# PI_Tank_level_controller.net
KiCad netlist of a schematic drawn in EAGLE
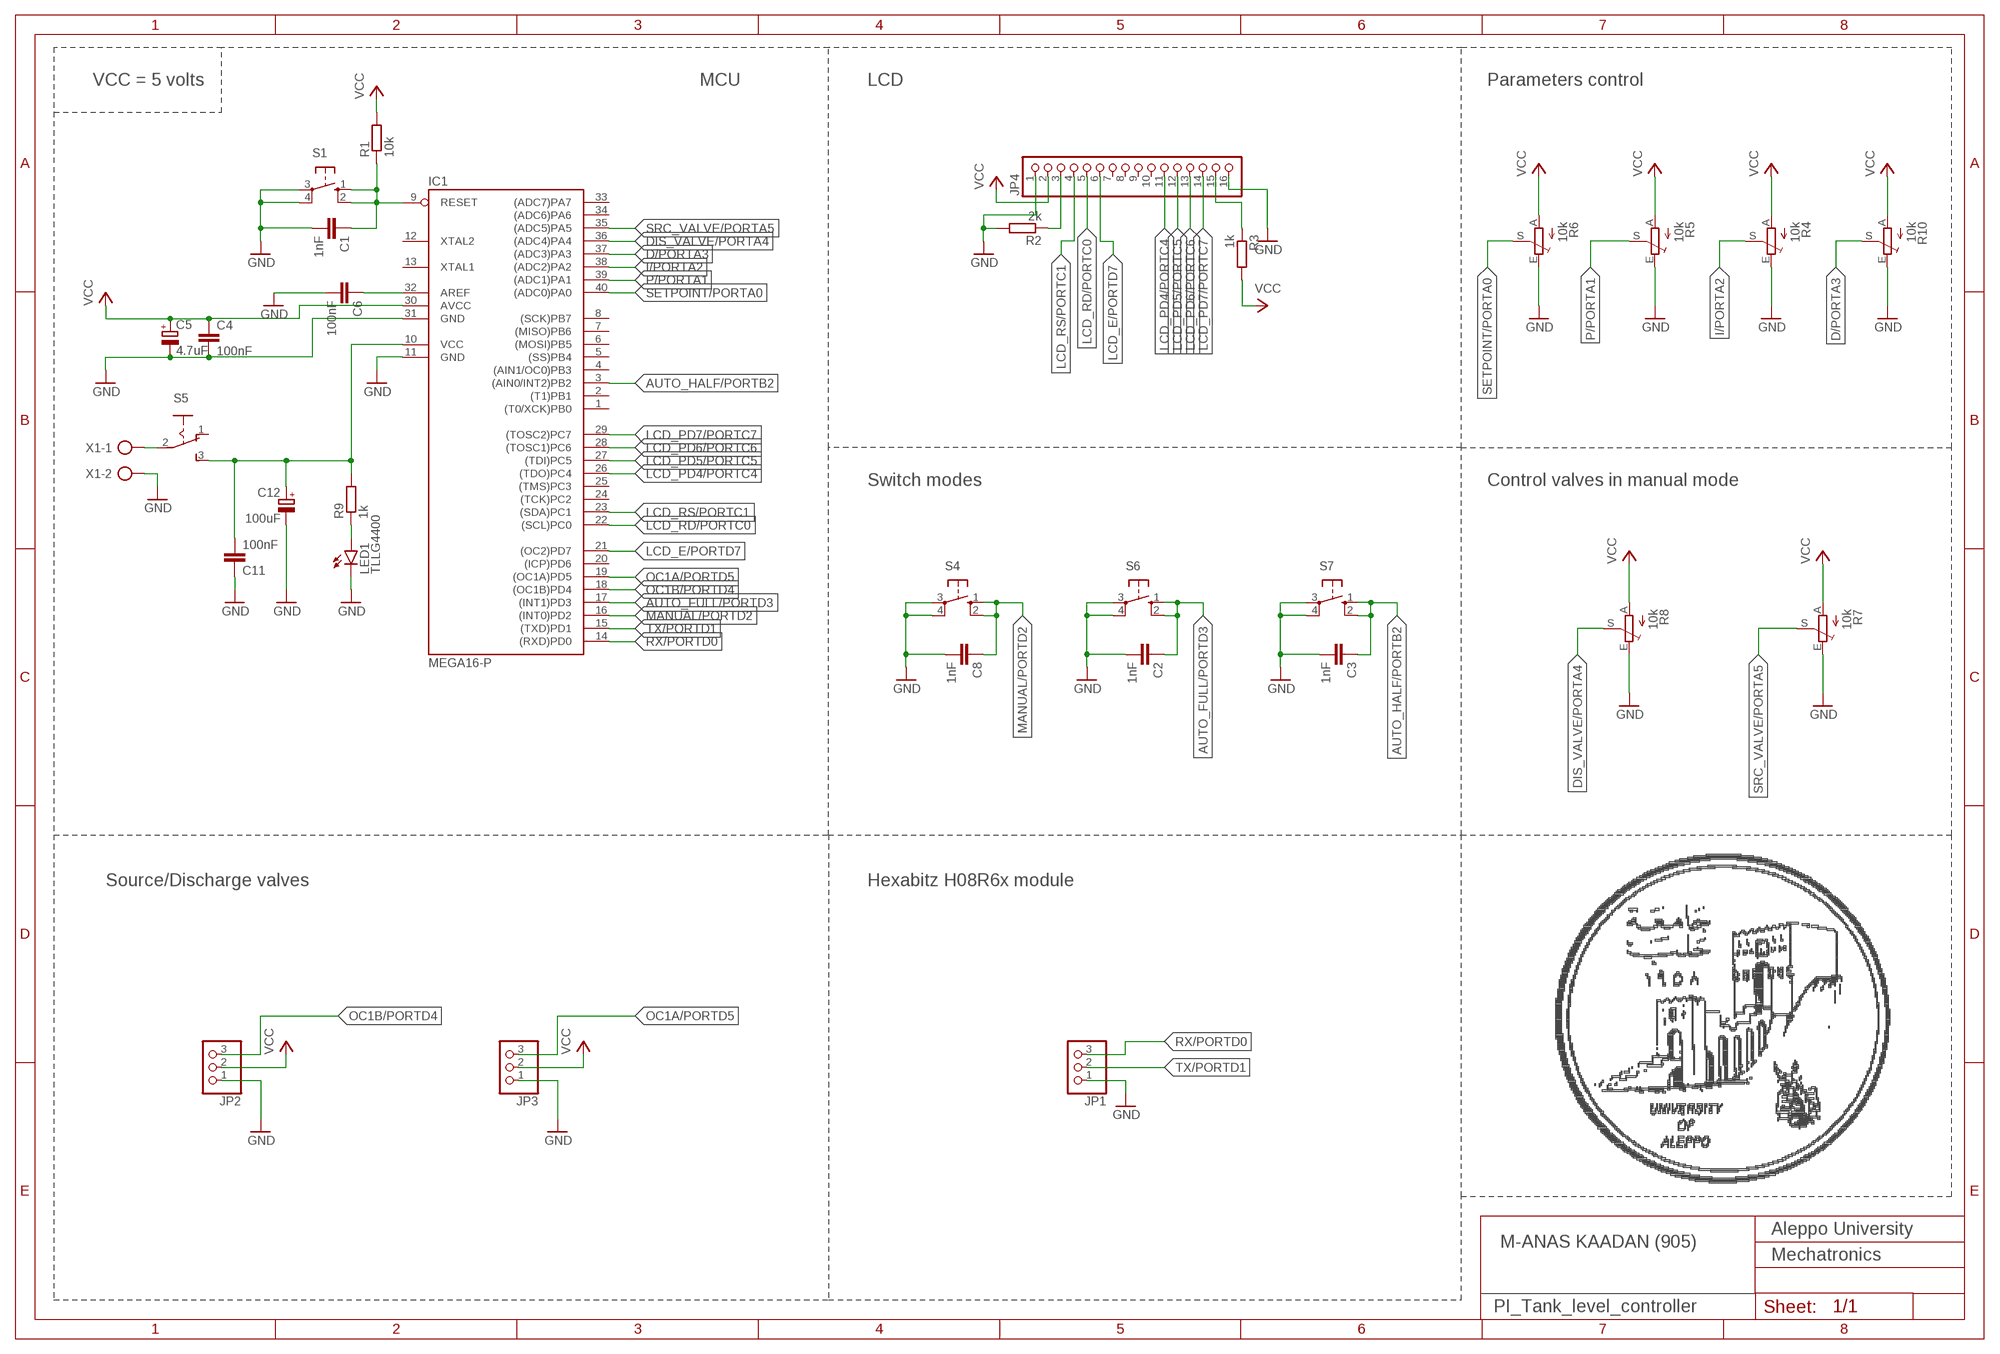
[diagram p0: schematic, sheet 1]

(export (version "E")
  (design (tool "Eeschema 10.0.6"))
  (components
    (comp (ref "C1")
      (value "1nF")
      (footprint "eagle-import:C025-024X044")
      (libsource (lib "eagle-import") (part "rcl_334_C-EU025-024X044"))
    )
    (comp (ref "C2")
      (value "1nF")
      (footprint "eagle-import:C025-024X044")
      (libsource (lib "eagle-import") (part "rcl_334_C-EU025-024X044"))
    )
    (comp (ref "C3")
      (value "1nF")
      (footprint "eagle-import:C025-024X044")
      (libsource (lib "eagle-import") (part "rcl_334_C-EU025-024X044"))
    )
    (comp (ref "C4")
      (value "100nF")
      (footprint "eagle-import:C025-024X044")
      (libsource (lib "eagle-import") (part "rcl_334_C-EU025-024X044"))
    )
    (comp (ref "C5")
      (value "4.7uF")
      (footprint "eagle-import:E2,5-6E")
      (libsource (lib "eagle-import") (part "rcl_334_CPOL-EUE2,5-6E"))
    )
    (comp (ref "C6")
      (value "100nF")
      (footprint "eagle-import:C025-024X044")
      (libsource (lib "eagle-import") (part "rcl_334_C-EU025-024X044"))
    )
    (comp (ref "C8")
      (value "1nF")
      (footprint "eagle-import:C025-024X044")
      (libsource (lib "eagle-import") (part "rcl_334_C-EU025-024X044"))
    )
    (comp (ref "C11")
      (value "100nF")
      (footprint "eagle-import:C025-024X044")
      (libsource (lib "eagle-import") (part "C-EU025-024X044"))
    )
    (comp (ref "C12")
      (value "100uF")
      (footprint "eagle-import:B45181A")
      (libsource (lib "eagle-import") (part "CPOL-EUB45181A"))
    )
    (comp (ref "IC1")
      (value "MEGA16-P")
      (footprint "eagle-import:DIL40")
      (fields (field (name "MPN") "ATMEGA16-16PU"))
      (libsource (lib "eagle-import") (part "MEGA16-P"))
    )
    (comp (ref "JP1")
      (value "PINHD-1X3")
      (footprint "eagle-import:1X03")
      (libsource (lib "eagle-import") (part "PINHD-1X3"))
    )
    (comp (ref "JP2")
      (value "PINHD-1X3")
      (footprint "eagle-import:1X03")
      (libsource (lib "eagle-import") (part "PINHD-1X3"))
    )
    (comp (ref "JP3")
      (value "PINHD-1X3")
      (footprint "eagle-import:1X03")
      (libsource (lib "eagle-import") (part "PINHD-1X3"))
    )
    (comp (ref "JP4")
      (value "PINHD-1X16")
      (footprint "eagle-import:1X16")
      (libsource (lib "eagle-import") (part "PINHD-1X16"))
    )
    (comp (ref "LED1")
      (value "TLLG4400")
      (footprint "eagle-import:LED3MM")
      (fields (field (name "MF") "VISHAY SEMICONDUCTOR"))
      (libsource (lib "eagle-import") (part "TLLG4400"))
    )
    (comp (ref "R1")
      (value "10k")
      (footprint "eagle-import:0204_7")
      (libsource (lib "eagle-import") (part "rcl_334_R-EU_0204/7"))
    )
    (comp (ref "R2")
      (value "2k")
      (footprint "eagle-import:0204_7")
      (libsource (lib "eagle-import") (part "rcl_334_R-EU_0204/7"))
    )
    (comp (ref "R3")
      (value "1k")
      (footprint "eagle-import:0204_7")
      (libsource (lib "eagle-import") (part "rcl_334_R-EU_0204/7"))
    )
    (comp (ref "R4")
      (value "10k")
      (footprint "eagle-import:RJ9W")
      (libsource (lib "eagle-import") (part "TRIM_EU-RJ9W"))
    )
    (comp (ref "R5")
      (value "10k")
      (footprint "eagle-import:RJ9W")
      (libsource (lib "eagle-import") (part "TRIM_EU-RJ9W"))
    )
    (comp (ref "R6")
      (value "10k")
      (footprint "eagle-import:RJ9W")
      (libsource (lib "eagle-import") (part "TRIM_EU-RJ9W"))
    )
    (comp (ref "R7")
      (value "10k")
      (footprint "eagle-import:RJ9W")
      (libsource (lib "eagle-import") (part "TRIM_EU-RJ9W"))
    )
    (comp (ref "R8")
      (value "10k")
      (footprint "eagle-import:RJ9W")
      (libsource (lib "eagle-import") (part "TRIM_EU-RJ9W"))
    )
    (comp (ref "R9")
      (value "1k")
      (footprint "eagle-import:0204_7")
      (libsource (lib "eagle-import") (part "R-EU_0204/7"))
    )
    (comp (ref "R10")
      (value "10k")
      (footprint "eagle-import:RJ9W")
      (libsource (lib "eagle-import") (part "TRIM_EU-RJ9W"))
    )
    (comp (ref "S1")
      (value "10-XX")
      (footprint "eagle-import:B3F-10XX")
      (fields (field (name "MPN") "B3F-1000"))
      (libsource (lib "eagle-import") (part "10-XX"))
    )
    (comp (ref "S4")
      (value "10-XX")
      (footprint "eagle-import:B3F-10XX")
      (fields (field (name "MPN") "B3F-1000"))
      (libsource (lib "eagle-import") (part "10-XX"))
    )
    (comp (ref "S5")
      (value "255SB")
      (footprint "eagle-import:255SB")
      (libsource (lib "eagle-import") (part "255SB"))
    )
    (comp (ref "S6")
      (value "10-XX")
      (footprint "eagle-import:B3F-10XX")
      (fields (field (name "MPN") "B3F-1000"))
      (libsource (lib "eagle-import") (part "10-XX"))
    )
    (comp (ref "S7")
      (value "10-XX")
      (footprint "eagle-import:B3F-10XX")
      (fields (field (name "MPN") "B3F-1000"))
      (libsource (lib "eagle-import") (part "10-XX"))
    )
    (comp (ref "X1")
      (value "AK300/2")
      (footprint "eagle-import:AK300_2")
      (libsource (lib "eagle-import") (part "AK300/2"))
    )
  )
  (nets
    (net (code "1") (name "AUTO_FULL{slash}PORTD3") (class "Default")
      (node (ref "C2") (pin "1") (pinfunction "1_1") (pintype "passive"))
      (node (ref "IC1") (pin "17") (pinfunction "(INT1)PD3_17") (pintype "bidirectional"))
      (node (ref "S6") (pin "1") (pinfunction "S_1") (pintype "passive"))
      (node (ref "S6") (pin "2") (pinfunction "S1_2") (pintype "passive"))
    )
    (net (code "2") (name "AUTO_HALF{slash}PORTB2") (class "Default")
      (node (ref "C3") (pin "1") (pinfunction "1_1") (pintype "passive"))
      (node (ref "IC1") (pin "3") (pinfunction "(AIN0/INT2)PB2_3") (pintype "bidirectional"))
      (node (ref "S7") (pin "1") (pinfunction "S_1") (pintype "passive"))
      (node (ref "S7") (pin "2") (pinfunction "S1_2") (pintype "passive"))
    )
    (net (code "3") (name "DIS_VALVE{slash}PORTA4") (class "Default")
      (node (ref "IC1") (pin "36") (pinfunction "(ADC4)PA4_36") (pintype "bidirectional"))
      (node (ref "R8") (pin "S") (pinfunction "S_S") (pintype "passive"))
    )
    (net (code "4") (name "D{slash}PORTA3") (class "Default")
      (node (ref "IC1") (pin "37") (pinfunction "(ADC3)PA3_37") (pintype "bidirectional"))
      (node (ref "R10") (pin "S") (pinfunction "S_S") (pintype "passive"))
    )
    (net (code "5") (name "GND") (class "Default")
      (node (ref "C1") (pin "2") (pinfunction "2_2") (pintype "passive"))
      (node (ref "C11") (pin "1") (pinfunction "1_1") (pintype "passive"))
      (node (ref "C12") (pin "-") (pinfunction "-_-") (pintype "passive"))
      (node (ref "C2") (pin "2") (pinfunction "2_2") (pintype "passive"))
      (node (ref "C3") (pin "2") (pinfunction "2_2") (pintype "passive"))
      (node (ref "C4") (pin "2") (pinfunction "2_2") (pintype "passive"))
      (node (ref "C5") (pin "-") (pinfunction "-_-") (pintype "passive"))
      (node (ref "C6") (pin "2") (pinfunction "2_2") (pintype "passive"))
      (node (ref "C8") (pin "2") (pinfunction "2_2") (pintype "passive"))
      (node (ref "IC1") (pin "11") (pinfunction "GND_11") (pintype "power_in"))
      (node (ref "IC1") (pin "31") (pinfunction "GND_31") (pintype "power_in"))
      (node (ref "JP1") (pin "1") (pinfunction "1_1") (pintype "passive"))
      (node (ref "JP2") (pin "1") (pinfunction "1_1") (pintype "passive"))
      (node (ref "JP3") (pin "1") (pinfunction "1_1") (pintype "passive"))
      (node (ref "JP4") (pin "1") (pinfunction "1_1") (pintype "passive"))
      (node (ref "JP4") (pin "16") (pinfunction "16_16") (pintype "passive"))
      (node (ref "LED1") (pin "K") (pinfunction "C_K") (pintype "passive"))
      (node (ref "R10") (pin "E") (pinfunction "E_E") (pintype "passive"))
      (node (ref "R2") (pin "2") (pinfunction "2_2") (pintype "passive"))
      (node (ref "R4") (pin "E") (pinfunction "E_E") (pintype "passive"))
      (node (ref "R5") (pin "E") (pinfunction "E_E") (pintype "passive"))
      (node (ref "R6") (pin "E") (pinfunction "E_E") (pintype "passive"))
      (node (ref "R7") (pin "E") (pinfunction "E_E") (pintype "passive"))
      (node (ref "R8") (pin "E") (pinfunction "E_E") (pintype "passive"))
      (node (ref "S1") (pin "3") (pinfunction "P_3") (pintype "passive"))
      (node (ref "S1") (pin "4") (pinfunction "P1_4") (pintype "passive"))
      (node (ref "S4") (pin "3") (pinfunction "P_3") (pintype "passive"))
      (node (ref "S4") (pin "4") (pinfunction "P1_4") (pintype "passive"))
      (node (ref "S6") (pin "3") (pinfunction "P_3") (pintype "passive"))
      (node (ref "S6") (pin "4") (pinfunction "P1_4") (pintype "passive"))
      (node (ref "S7") (pin "3") (pinfunction "P_3") (pintype "passive"))
      (node (ref "S7") (pin "4") (pinfunction "P1_4") (pintype "passive"))
      (node (ref "X1") (pin "2") (pinfunction "KL_2") (pintype "passive"))
    )
    (net (code "6") (name "I{slash}PORTA2") (class "Default")
      (node (ref "IC1") (pin "38") (pinfunction "(ADC2)PA2_38") (pintype "bidirectional"))
      (node (ref "R4") (pin "S") (pinfunction "S_S") (pintype "passive"))
    )
    (net (code "7") (name "LCD_E{slash}PORTD7") (class "Default")
      (node (ref "IC1") (pin "21") (pinfunction "(OC2)PD7_21") (pintype "bidirectional"))
      (node (ref "JP4") (pin "6") (pinfunction "6_6") (pintype "passive"))
    )
    (net (code "8") (name "LCD_PD4{slash}PORTC4") (class "Default")
      (node (ref "IC1") (pin "26") (pinfunction "(TDO)PC4_26") (pintype "bidirectional"))
      (node (ref "JP4") (pin "11") (pinfunction "11_11") (pintype "passive"))
    )
    (net (code "9") (name "LCD_PD5{slash}PORTC5") (class "Default")
      (node (ref "IC1") (pin "27") (pinfunction "(TDI)PC5_27") (pintype "bidirectional"))
      (node (ref "JP4") (pin "12") (pinfunction "12_12") (pintype "passive"))
    )
    (net (code "10") (name "LCD_PD6{slash}PORTC6") (class "Default")
      (node (ref "IC1") (pin "28") (pinfunction "(TOSC1)PC6_28") (pintype "bidirectional"))
      (node (ref "JP4") (pin "13") (pinfunction "13_13") (pintype "passive"))
    )
    (net (code "11") (name "LCD_PD7{slash}PORTC7") (class "Default")
      (node (ref "IC1") (pin "29") (pinfunction "(TOSC2)PC7_29") (pintype "bidirectional"))
      (node (ref "JP4") (pin "14") (pinfunction "14_14") (pintype "passive"))
    )
    (net (code "12") (name "LCD_RD{slash}PORTC0") (class "Default")
      (node (ref "IC1") (pin "22") (pinfunction "(SCL)PC0_22") (pintype "bidirectional"))
      (node (ref "JP4") (pin "5") (pinfunction "5_5") (pintype "passive"))
    )
    (net (code "13") (name "LCD_RS{slash}PORTC1") (class "Default")
      (node (ref "IC1") (pin "23") (pinfunction "(SDA)PC1_23") (pintype "bidirectional"))
      (node (ref "JP4") (pin "4") (pinfunction "4_4") (pintype "passive"))
    )
    (net (code "14") (name "MANUAL{slash}PORTD2") (class "Default")
      (node (ref "C8") (pin "1") (pinfunction "1_1") (pintype "passive"))
      (node (ref "IC1") (pin "16") (pinfunction "(INT0)PD2_16") (pintype "bidirectional"))
      (node (ref "S4") (pin "1") (pinfunction "S_1") (pintype "passive"))
      (node (ref "S4") (pin "2") (pinfunction "S1_2") (pintype "passive"))
    )
    (net (code "15") (name "Net-(IC1-AREF)") (class "Default")
      (node (ref "C6") (pin "1") (pinfunction "1_1") (pintype "passive"))
      (node (ref "IC1") (pin "32") (pinfunction "AREF_32") (pintype "passive"))
    )
    (net (code "16") (name "Net-(IC1-RESET)") (class "Default")
      (node (ref "C1") (pin "1") (pinfunction "1_1") (pintype "passive"))
      (node (ref "IC1") (pin "9") (pinfunction "RESET_9") (pintype "input"))
      (node (ref "R1") (pin "1") (pinfunction "1_1") (pintype "passive"))
      (node (ref "S1") (pin "1") (pinfunction "S_1") (pintype "passive"))
      (node (ref "S1") (pin "2") (pinfunction "S1_2") (pintype "passive"))
    )
    (net (code "17") (name "Net-(JP4-Pad3)") (class "Default")
      (node (ref "JP4") (pin "3") (pinfunction "3_3") (pintype "passive"))
      (node (ref "R2") (pin "1") (pinfunction "1_1") (pintype "passive"))
    )
    (net (code "18") (name "Net-(JP4-Pad15)") (class "Default")
      (node (ref "JP4") (pin "15") (pinfunction "15_15") (pintype "passive"))
      (node (ref "R3") (pin "1") (pinfunction "1_1") (pintype "passive"))
    )
    (net (code "19") (name "Net-(LED1-PadA)") (class "Default")
      (node (ref "LED1") (pin "A") (pinfunction "A_A") (pintype "passive"))
      (node (ref "R9") (pin "1") (pinfunction "1_1") (pintype "passive"))
    )
    (net (code "20") (name "Net-(S5-P)") (class "Default")
      (node (ref "S5") (pin "2") (pinfunction "P_2") (pintype "passive"))
      (node (ref "X1") (pin "1") (pinfunction "KL_1") (pintype "passive"))
    )
    (net (code "21") (name "OC1A{slash}PORTD5") (class "Default")
      (node (ref "IC1") (pin "19") (pinfunction "(OC1A)PD5_19") (pintype "bidirectional"))
      (node (ref "JP3") (pin "3") (pinfunction "3_3") (pintype "passive"))
    )
    (net (code "22") (name "OC1B{slash}PORTD4") (class "Default")
      (node (ref "IC1") (pin "18") (pinfunction "(OC1B)PD4_18") (pintype "bidirectional"))
      (node (ref "JP2") (pin "3") (pinfunction "3_3") (pintype "passive"))
    )
    (net (code "23") (name "P{slash}PORTA1") (class "Default")
      (node (ref "IC1") (pin "39") (pinfunction "(ADC1)PA1_39") (pintype "bidirectional"))
      (node (ref "R5") (pin "S") (pinfunction "S_S") (pintype "passive"))
    )
    (net (code "24") (name "RX{slash}PORTD0") (class "Default")
      (node (ref "IC1") (pin "14") (pinfunction "(RXD)PD0_14") (pintype "bidirectional"))
      (node (ref "JP1") (pin "3") (pinfunction "3_3") (pintype "passive"))
    )
    (net (code "25") (name "SETPOINT{slash}PORTA0") (class "Default")
      (node (ref "IC1") (pin "40") (pinfunction "(ADC0)PA0_40") (pintype "bidirectional"))
      (node (ref "R6") (pin "S") (pinfunction "S_S") (pintype "passive"))
    )
    (net (code "26") (name "SRC_VALVE{slash}PORTA5") (class "Default")
      (node (ref "IC1") (pin "35") (pinfunction "(ADC5)PA5_35") (pintype "bidirectional"))
      (node (ref "R7") (pin "S") (pinfunction "S_S") (pintype "passive"))
    )
    (net (code "27") (name "TX{slash}PORTD1") (class "Default")
      (node (ref "IC1") (pin "15") (pinfunction "(TXD)PD1_15") (pintype "bidirectional"))
      (node (ref "JP1") (pin "2") (pinfunction "2_2") (pintype "passive"))
    )
    (net (code "28") (name "VCC") (class "Default")
      (node (ref "C11") (pin "2") (pinfunction "2_2") (pintype "passive"))
      (node (ref "C12") (pin "+") (pinfunction "+_+") (pintype "passive"))
      (node (ref "C4") (pin "1") (pinfunction "1_1") (pintype "passive"))
      (node (ref "C5") (pin "+") (pinfunction "+_+") (pintype "passive"))
      (node (ref "IC1") (pin "10") (pinfunction "VCC_10") (pintype "power_in"))
      (node (ref "IC1") (pin "30") (pinfunction "AVCC_30") (pintype "power_in"))
      (node (ref "JP2") (pin "2") (pinfunction "2_2") (pintype "passive"))
      (node (ref "JP3") (pin "2") (pinfunction "2_2") (pintype "passive"))
      (node (ref "JP4") (pin "2") (pinfunction "2_2") (pintype "passive"))
      (node (ref "R1") (pin "2") (pinfunction "2_2") (pintype "passive"))
      (node (ref "R10") (pin "A") (pinfunction "A_A") (pintype "passive"))
      (node (ref "R3") (pin "2") (pinfunction "2_2") (pintype "passive"))
      (node (ref "R4") (pin "A") (pinfunction "A_A") (pintype "passive"))
      (node (ref "R5") (pin "A") (pinfunction "A_A") (pintype "passive"))
      (node (ref "R6") (pin "A") (pinfunction "A_A") (pintype "passive"))
      (node (ref "R7") (pin "A") (pinfunction "A_A") (pintype "passive"))
      (node (ref "R8") (pin "A") (pinfunction "A_A") (pintype "passive"))
      (node (ref "R9") (pin "2") (pinfunction "2_2") (pintype "passive"))
      (node (ref "S5") (pin "3") (pinfunction "S_3") (pintype "passive"))
    )
    (net (code "29") (name "unconnected-(IC1-(ADC6)PA6-Pad34)") (class "Default")
      (node (ref "IC1") (pin "34") (pinfunction "(ADC6)PA6_34") (pintype "bidirectional"))
    )
    (net (code "30") (name "unconnected-(IC1-(ADC7)PA7-Pad33)") (class "Default")
      (node (ref "IC1") (pin "33") (pinfunction "(ADC7)PA7_33") (pintype "bidirectional"))
    )
    (net (code "31") (name "unconnected-(IC1-(AIN1{slash}OC0)PB3-Pad4)") (class "Default")
      (node (ref "IC1") (pin "4") (pinfunction "(AIN1/OC0)PB3_4") (pintype "bidirectional"))
    )
    (net (code "32") (name "unconnected-(IC1-(ICP)PD6-Pad20)") (class "Default")
      (node (ref "IC1") (pin "20") (pinfunction "(ICP)PD6_20") (pintype "bidirectional"))
    )
    (net (code "33") (name "unconnected-(IC1-(MISO)PB6-Pad7)") (class "Default")
      (node (ref "IC1") (pin "7") (pinfunction "(MISO)PB6_7") (pintype "bidirectional"))
    )
    (net (code "34") (name "unconnected-(IC1-(MOSI)PB5-Pad6)") (class "Default")
      (node (ref "IC1") (pin "6") (pinfunction "(MOSI)PB5_6") (pintype "bidirectional"))
    )
    (net (code "35") (name "unconnected-(IC1-(SCK)PB7-Pad8)") (class "Default")
      (node (ref "IC1") (pin "8") (pinfunction "(SCK)PB7_8") (pintype "bidirectional"))
    )
    (net (code "36") (name "unconnected-(IC1-(SS)PB4-Pad5)") (class "Default")
      (node (ref "IC1") (pin "5") (pinfunction "(SS)PB4_5") (pintype "bidirectional"))
    )
    (net (code "37") (name "unconnected-(IC1-(T0{slash}XCK)PB0-Pad1)") (class "Default")
      (node (ref "IC1") (pin "1") (pinfunction "(T0/XCK)PB0_1") (pintype "bidirectional"))
    )
    (net (code "38") (name "unconnected-(IC1-(T1)PB1-Pad2)") (class "Default")
      (node (ref "IC1") (pin "2") (pinfunction "(T1)PB1_2") (pintype "bidirectional"))
    )
    (net (code "39") (name "unconnected-(IC1-(TCK)PC2-Pad24)") (class "Default")
      (node (ref "IC1") (pin "24") (pinfunction "(TCK)PC2_24") (pintype "bidirectional"))
    )
    (net (code "40") (name "unconnected-(IC1-(TMS)PC3-Pad25)") (class "Default")
      (node (ref "IC1") (pin "25") (pinfunction "(TMS)PC3_25") (pintype "bidirectional"))
    )
    (net (code "41") (name "unconnected-(IC1-XTAL1-Pad13)") (class "Default")
      (node (ref "IC1") (pin "13") (pinfunction "XTAL1_13") (pintype "bidirectional"))
    )
    (net (code "42") (name "unconnected-(IC1-XTAL2-Pad12)") (class "Default")
      (node (ref "IC1") (pin "12") (pinfunction "XTAL2_12") (pintype "bidirectional"))
    )
    (net (code "43") (name "unconnected-(JP4-Pad7)") (class "Default")
      (node (ref "JP4") (pin "7") (pinfunction "7_7") (pintype "passive"))
    )
    (net (code "44") (name "unconnected-(JP4-Pad8)") (class "Default")
      (node (ref "JP4") (pin "8") (pinfunction "8_8") (pintype "passive"))
    )
    (net (code "45") (name "unconnected-(JP4-Pad9)") (class "Default")
      (node (ref "JP4") (pin "9") (pinfunction "9_9") (pintype "passive"))
    )
    (net (code "46") (name "unconnected-(JP4-Pad10)") (class "Default")
      (node (ref "JP4") (pin "10") (pinfunction "10_10") (pintype "passive"))
    )
    (net (code "47") (name "unconnected-(S5-O-Pad1)") (class "Default")
      (node (ref "S5") (pin "1") (pinfunction "O_1") (pintype "passive"))
    )
  )
)
